# SOLEDNOID.net
KiCad netlist of a schematic drawn in Altium Designer
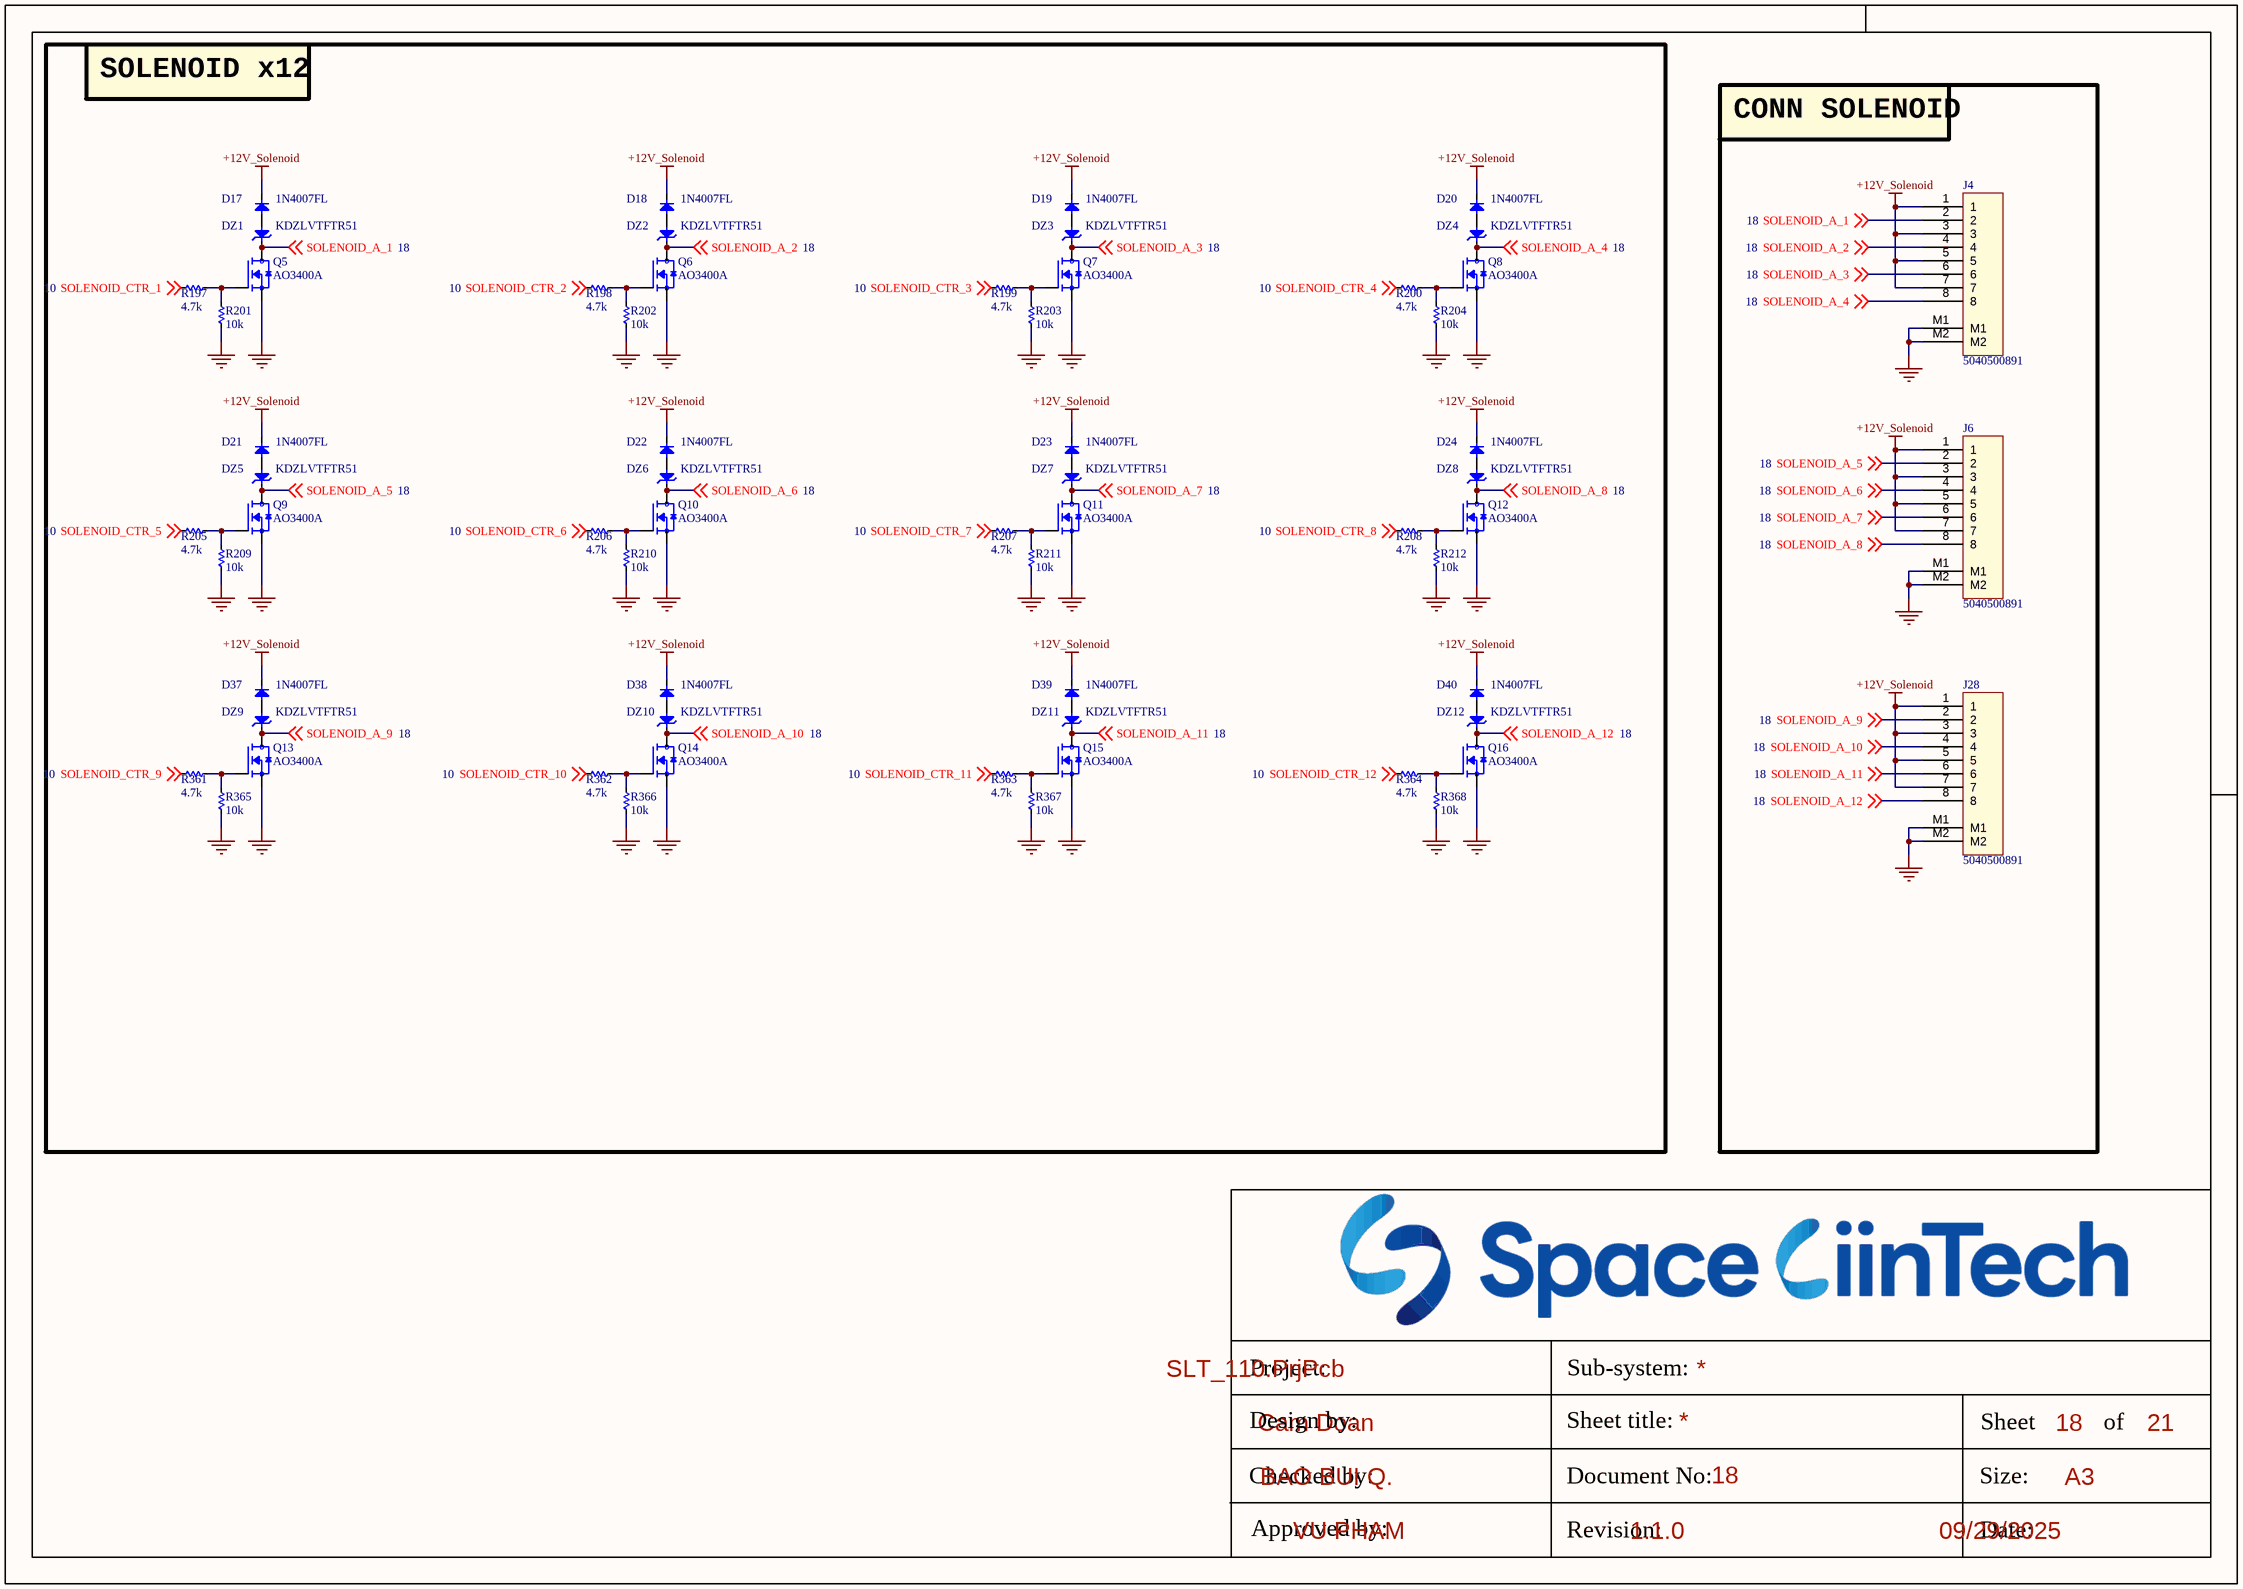
[diagram p0: SOLEDNOID.SchDoc]

(export (version "E")
  (design (tool "Eeschema 10.0.6"))
  (components
    (comp (ref "D17")
      (value "1N4007FL")
      (footprint "SOD3717X145N")
      (description "Default Diode")
      (fields (field (name "PUBLISHER") "Altium Limited"))
      (libsource (lib "LABLIB") (part "Diode SMD"))
    )
    (comp (ref "D18")
      (value "1N4007FL")
      (footprint "SOD3717X145N")
      (description "Default Diode")
      (fields (field (name "PUBLISHER") "Altium Limited"))
      (libsource (lib "LABLIB") (part "Diode SMD"))
    )
    (comp (ref "D19")
      (value "1N4007FL")
      (footprint "SOD3717X145N")
      (description "Default Diode")
      (fields (field (name "PUBLISHER") "Altium Limited"))
      (libsource (lib "LABLIB") (part "Diode SMD"))
    )
    (comp (ref "D20")
      (value "1N4007FL")
      (footprint "SOD3717X145N")
      (description "Default Diode")
      (fields (field (name "PUBLISHER") "Altium Limited"))
      (libsource (lib "LABLIB") (part "Diode SMD"))
    )
    (comp (ref "D21")
      (value "1N4007FL")
      (footprint "SOD3717X145N")
      (description "Default Diode")
      (fields (field (name "PUBLISHER") "Altium Limited"))
      (libsource (lib "LABLIB") (part "Diode SMD"))
    )
    (comp (ref "D22")
      (value "1N4007FL")
      (footprint "SOD3717X145N")
      (description "Default Diode")
      (fields (field (name "PUBLISHER") "Altium Limited"))
      (libsource (lib "LABLIB") (part "Diode SMD"))
    )
    (comp (ref "D23")
      (value "1N4007FL")
      (footprint "SOD3717X145N")
      (description "Default Diode")
      (fields (field (name "PUBLISHER") "Altium Limited"))
      (libsource (lib "LABLIB") (part "Diode SMD"))
    )
    (comp (ref "D24")
      (value "1N4007FL")
      (footprint "SOD3717X145N")
      (description "Default Diode")
      (fields (field (name "PUBLISHER") "Altium Limited"))
      (libsource (lib "LABLIB") (part "Diode SMD"))
    )
    (comp (ref "D37")
      (value "1N4007FL")
      (footprint "SOD3717X145N")
      (description "Default Diode")
      (fields (field (name "PUBLISHER") "Altium Limited"))
      (libsource (lib "LABLIB") (part "Diode SMD"))
    )
    (comp (ref "D38")
      (value "1N4007FL")
      (footprint "SOD3717X145N")
      (description "Default Diode")
      (fields (field (name "PUBLISHER") "Altium Limited"))
      (libsource (lib "LABLIB") (part "Diode SMD"))
    )
    (comp (ref "D39")
      (value "1N4007FL")
      (footprint "SOD3717X145N")
      (description "Default Diode")
      (fields (field (name "PUBLISHER") "Altium Limited"))
      (libsource (lib "LABLIB") (part "Diode SMD"))
    )
    (comp (ref "D40")
      (value "1N4007FL")
      (footprint "SOD3717X145N")
      (description "Default Diode")
      (fields (field (name "PUBLISHER") "Altium Limited"))
      (libsource (lib "LABLIB") (part "Diode SMD"))
    )
    (comp (ref "DZ1")
      (value "KDZLVTFTR51")
      (footprint "SOD3717X145N")
      (description "Zenner")
      (libsource (lib "LABLIB") (part "DIODE Zener"))
    )
    (comp (ref "DZ2")
      (value "KDZLVTFTR51")
      (footprint "SOD3717X145N")
      (description "Zenner")
      (libsource (lib "LABLIB") (part "DIODE Zener"))
    )
    (comp (ref "DZ3")
      (value "KDZLVTFTR51")
      (footprint "SOD3717X145N")
      (description "Zenner")
      (libsource (lib "LABLIB") (part "DIODE Zener"))
    )
    (comp (ref "DZ4")
      (value "KDZLVTFTR51")
      (footprint "SOD3717X145N")
      (description "Zenner")
      (libsource (lib "LABLIB") (part "DIODE Zener"))
    )
    (comp (ref "DZ5")
      (value "KDZLVTFTR51")
      (footprint "SOD3717X145N")
      (description "Zenner")
      (libsource (lib "LABLIB") (part "DIODE Zener"))
    )
    (comp (ref "DZ6")
      (value "KDZLVTFTR51")
      (footprint "SOD3717X145N")
      (description "Zenner")
      (libsource (lib "LABLIB") (part "DIODE Zener"))
    )
    (comp (ref "DZ7")
      (value "KDZLVTFTR51")
      (footprint "SOD3717X145N")
      (description "Zenner")
      (libsource (lib "LABLIB") (part "DIODE Zener"))
    )
    (comp (ref "DZ8")
      (value "KDZLVTFTR51")
      (footprint "SOD3717X145N")
      (description "Zenner")
      (libsource (lib "LABLIB") (part "DIODE Zener"))
    )
    (comp (ref "DZ9")
      (value "KDZLVTFTR51")
      (footprint "SOD3717X145N")
      (description "Zenner")
      (libsource (lib "LABLIB") (part "DIODE Zener"))
    )
    (comp (ref "DZ10")
      (value "KDZLVTFTR51")
      (footprint "SOD3717X145N")
      (description "Zenner")
      (libsource (lib "LABLIB") (part "DIODE Zener"))
    )
    (comp (ref "DZ11")
      (value "KDZLVTFTR51")
      (footprint "SOD3717X145N")
      (description "Zenner")
      (libsource (lib "LABLIB") (part "DIODE Zener"))
    )
    (comp (ref "DZ12")
      (value "KDZLVTFTR51")
      (footprint "SOD3717X145N")
      (description "Zenner")
      (libsource (lib "LABLIB") (part "DIODE Zener"))
    )
    (comp (ref "J4")
      (value "5040500891")
      (footprint "MOLEX_5040500891")
      (libsource (lib "LABLIB") (part "Header 8x1_2M"))
    )
    (comp (ref "J6")
      (value "5040500891")
      (footprint "MOLEX_5040500891")
      (libsource (lib "LABLIB") (part "Header 8x1_2M"))
    )
    (comp (ref "J28")
      (value "5040500891")
      (footprint "MOLEX_5040500891")
      (libsource (lib "LABLIB") (part "Header 8x1_2M"))
    )
    (comp (ref "Q5")
      (value "AO3400A")
      (footprint "SOT95P240X120-3N")
      (description "N-Channel 30 V 5.7A (Ta) 1.4W (Ta) Surface Mount SOT-23-3")
      (fields (field (name "MF") "Alpha & Omega Semiconductor"))
      (libsource (lib "new_component") (part "MOSFET_N"))
    )
    (comp (ref "Q6")
      (value "AO3400A")
      (footprint "SOT95P240X120-3N")
      (description "N-Channel 30 V 5.7A (Ta) 1.4W (Ta) Surface Mount SOT-23-3")
      (fields (field (name "MF") "Alpha & Omega Semiconductor"))
      (libsource (lib "new_component") (part "MOSFET_N"))
    )
    (comp (ref "Q7")
      (value "AO3400A")
      (footprint "SOT95P240X120-3N")
      (description "N-Channel 30 V 5.7A (Ta) 1.4W (Ta) Surface Mount SOT-23-3")
      (fields (field (name "MF") "Alpha & Omega Semiconductor"))
      (libsource (lib "new_component") (part "MOSFET_N"))
    )
    (comp (ref "Q8")
      (value "AO3400A")
      (footprint "SOT95P240X120-3N")
      (description "N-Channel 30 V 5.7A (Ta) 1.4W (Ta) Surface Mount SOT-23-3")
      (fields (field (name "MF") "Alpha & Omega Semiconductor"))
      (libsource (lib "new_component") (part "MOSFET_N"))
    )
    (comp (ref "Q9")
      (value "AO3400A")
      (footprint "SOT95P240X120-3N")
      (description "N-Channel 30 V 5.7A (Ta) 1.4W (Ta) Surface Mount SOT-23-3")
      (fields (field (name "MF") "Alpha & Omega Semiconductor"))
      (libsource (lib "new_component") (part "MOSFET_N"))
    )
    (comp (ref "Q10")
      (value "AO3400A")
      (footprint "SOT95P240X120-3N")
      (description "N-Channel 30 V 5.7A (Ta) 1.4W (Ta) Surface Mount SOT-23-3")
      (fields (field (name "MF") "Alpha & Omega Semiconductor"))
      (libsource (lib "new_component") (part "MOSFET_N"))
    )
    (comp (ref "Q11")
      (value "AO3400A")
      (footprint "SOT95P240X120-3N")
      (description "N-Channel 30 V 5.7A (Ta) 1.4W (Ta) Surface Mount SOT-23-3")
      (fields (field (name "MF") "Alpha & Omega Semiconductor"))
      (libsource (lib "new_component") (part "MOSFET_N"))
    )
    (comp (ref "Q12")
      (value "AO3400A")
      (footprint "SOT95P240X120-3N")
      (description "N-Channel 30 V 5.7A (Ta) 1.4W (Ta) Surface Mount SOT-23-3")
      (fields (field (name "MF") "Alpha & Omega Semiconductor"))
      (libsource (lib "new_component") (part "MOSFET_N"))
    )
    (comp (ref "Q13")
      (value "AO3400A")
      (footprint "SOT95P240X120-3N")
      (description "N-Channel 30 V 5.7A (Ta) 1.4W (Ta) Surface Mount SOT-23-3")
      (fields (field (name "MF") "Alpha & Omega Semiconductor"))
      (libsource (lib "new_component") (part "MOSFET_N"))
    )
    (comp (ref "Q14")
      (value "AO3400A")
      (footprint "SOT95P240X120-3N")
      (description "N-Channel 30 V 5.7A (Ta) 1.4W (Ta) Surface Mount SOT-23-3")
      (fields (field (name "MF") "Alpha & Omega Semiconductor"))
      (libsource (lib "new_component") (part "MOSFET_N"))
    )
    (comp (ref "Q15")
      (value "AO3400A")
      (footprint "SOT95P240X120-3N")
      (description "N-Channel 30 V 5.7A (Ta) 1.4W (Ta) Surface Mount SOT-23-3")
      (fields (field (name "MF") "Alpha & Omega Semiconductor"))
      (libsource (lib "new_component") (part "MOSFET_N"))
    )
    (comp (ref "Q16")
      (value "AO3400A")
      (footprint "SOT95P240X120-3N")
      (description "N-Channel 30 V 5.7A (Ta) 1.4W (Ta) Surface Mount SOT-23-3")
      (fields (field (name "MF") "Alpha & Omega Semiconductor"))
      (libsource (lib "new_component") (part "MOSFET_N"))
    )
    (comp (ref "R197")
      (value "4.7k")
      (footprint "RES_C_1005X40")
      (description "RES")
      (libsource (lib "LABLIB") (part "_RES_B_2"))
    )
    (comp (ref "R198")
      (value "4.7k")
      (footprint "RES_C_1005X40")
      (description "RES")
      (libsource (lib "LABLIB") (part "_RES_B_2"))
    )
    (comp (ref "R199")
      (value "4.7k")
      (footprint "RES_C_1005X40")
      (description "RES")
      (libsource (lib "LABLIB") (part "_RES_B_2"))
    )
    (comp (ref "R200")
      (value "4.7k")
      (footprint "RES_C_1005X40")
      (description "RES")
      (libsource (lib "LABLIB") (part "_RES_B_2"))
    )
    (comp (ref "R201")
      (value "10k")
      (footprint "RES_C_1005X40")
      (description "RES")
      (libsource (lib "LABLIB") (part "_RES_B_2"))
    )
    (comp (ref "R202")
      (value "10k")
      (footprint "RES_C_1005X40")
      (description "RES")
      (libsource (lib "LABLIB") (part "_RES_B_2"))
    )
    (comp (ref "R203")
      (value "10k")
      (footprint "RES_C_1005X40")
      (description "RES")
      (libsource (lib "LABLIB") (part "_RES_B_2"))
    )
    (comp (ref "R204")
      (value "10k")
      (footprint "RES_C_1005X40")
      (description "RES")
      (libsource (lib "LABLIB") (part "_RES_B_2"))
    )
    (comp (ref "R205")
      (value "4.7k")
      (footprint "RES_C_1005X40")
      (description "RES")
      (libsource (lib "LABLIB") (part "_RES_B_2"))
    )
    (comp (ref "R206")
      (value "4.7k")
      (footprint "RES_C_1005X40")
      (description "RES")
      (libsource (lib "LABLIB") (part "_RES_B_2"))
    )
    (comp (ref "R207")
      (value "4.7k")
      (footprint "RES_C_1005X40")
      (description "RES")
      (libsource (lib "LABLIB") (part "_RES_B_2"))
    )
    (comp (ref "R208")
      (value "4.7k")
      (footprint "RES_C_1005X40")
      (description "RES")
      (libsource (lib "LABLIB") (part "_RES_B_2"))
    )
    (comp (ref "R209")
      (value "10k")
      (footprint "RES_C_1005X40")
      (description "RES")
      (libsource (lib "LABLIB") (part "_RES_B_2"))
    )
    (comp (ref "R210")
      (value "10k")
      (footprint "RES_C_1005X40")
      (description "RES")
      (libsource (lib "LABLIB") (part "_RES_B_2"))
    )
    (comp (ref "R211")
      (value "10k")
      (footprint "RES_C_1005X40")
      (description "RES")
      (libsource (lib "LABLIB") (part "_RES_B_2"))
    )
    (comp (ref "R212")
      (value "10k")
      (footprint "RES_C_1005X40")
      (description "RES")
      (libsource (lib "LABLIB") (part "_RES_B_2"))
    )
    (comp (ref "R361")
      (value "4.7k")
      (footprint "RES_C_1005X40")
      (description "RES")
      (libsource (lib "LABLIB") (part "_RES_B_2"))
    )
    (comp (ref "R362")
      (value "4.7k")
      (footprint "RES_C_1005X40")
      (description "RES")
      (libsource (lib "LABLIB") (part "_RES_B_2"))
    )
    (comp (ref "R363")
      (value "4.7k")
      (footprint "RES_C_1005X40")
      (description "RES")
      (libsource (lib "LABLIB") (part "_RES_B_2"))
    )
    (comp (ref "R364")
      (value "4.7k")
      (footprint "RES_C_1005X40")
      (description "RES")
      (libsource (lib "LABLIB") (part "_RES_B_2"))
    )
    (comp (ref "R365")
      (value "10k")
      (footprint "RES_C_1005X40")
      (description "RES")
      (libsource (lib "LABLIB") (part "_RES_B_2"))
    )
    (comp (ref "R366")
      (value "10k")
      (footprint "RES_C_1005X40")
      (description "RES")
      (libsource (lib "LABLIB") (part "_RES_B_2"))
    )
    (comp (ref "R367")
      (value "10k")
      (footprint "RES_C_1005X40")
      (description "RES")
      (libsource (lib "LABLIB") (part "_RES_B_2"))
    )
    (comp (ref "R368")
      (value "10k")
      (footprint "RES_C_1005X40")
      (description "RES")
      (libsource (lib "LABLIB") (part "_RES_B_2"))
    )
  )
  (nets
    (net (code "1") (name "+12V_Solenoid") (class "Default")
      (node (ref "D17") (pin "1") (pinfunction "K_1") (pintype "passive"))
      (node (ref "D18") (pin "1") (pinfunction "K_1") (pintype "passive"))
      (node (ref "D19") (pin "1") (pinfunction "K_1") (pintype "passive"))
      (node (ref "D20") (pin "1") (pinfunction "K_1") (pintype "passive"))
      (node (ref "D21") (pin "1") (pinfunction "K_1") (pintype "passive"))
      (node (ref "D22") (pin "1") (pinfunction "K_1") (pintype "passive"))
      (node (ref "D23") (pin "1") (pinfunction "K_1") (pintype "passive"))
      (node (ref "D24") (pin "1") (pinfunction "K_1") (pintype "passive"))
      (node (ref "D37") (pin "1") (pinfunction "K_1") (pintype "passive"))
      (node (ref "D38") (pin "1") (pinfunction "K_1") (pintype "passive"))
      (node (ref "D39") (pin "1") (pinfunction "K_1") (pintype "passive"))
      (node (ref "D40") (pin "1") (pinfunction "K_1") (pintype "passive"))
      (node (ref "J28") (pin "1") (pinfunction "1_1") (pintype "passive"))
      (node (ref "J28") (pin "3") (pinfunction "3_3") (pintype "passive"))
      (node (ref "J28") (pin "5") (pinfunction "5_5") (pintype "passive"))
      (node (ref "J28") (pin "7") (pinfunction "7_7") (pintype "passive"))
      (node (ref "J4") (pin "1") (pinfunction "1_1") (pintype "passive"))
      (node (ref "J4") (pin "3") (pinfunction "3_3") (pintype "passive"))
      (node (ref "J4") (pin "5") (pinfunction "5_5") (pintype "passive"))
      (node (ref "J4") (pin "7") (pinfunction "7_7") (pintype "passive"))
      (node (ref "J6") (pin "1") (pinfunction "1_1") (pintype "passive"))
      (node (ref "J6") (pin "3") (pinfunction "3_3") (pintype "passive"))
      (node (ref "J6") (pin "5") (pinfunction "5_5") (pintype "passive"))
      (node (ref "J6") (pin "7") (pinfunction "7_7") (pintype "passive"))
    )
    (net (code "2") (name "GND") (class "Default")
      (node (ref "J28") (pin "M1") (pinfunction "M1_M1") (pintype "passive"))
      (node (ref "J28") (pin "M2") (pinfunction "M2_M2") (pintype "passive"))
      (node (ref "J4") (pin "M1") (pinfunction "M1_M1") (pintype "passive"))
      (node (ref "J4") (pin "M2") (pinfunction "M2_M2") (pintype "passive"))
      (node (ref "J6") (pin "M1") (pinfunction "M1_M1") (pintype "passive"))
      (node (ref "J6") (pin "M2") (pinfunction "M2_M2") (pintype "passive"))
      (node (ref "Q10") (pin "2") (pinfunction "S_2") (pintype "passive"))
      (node (ref "Q11") (pin "2") (pinfunction "S_2") (pintype "passive"))
      (node (ref "Q12") (pin "2") (pinfunction "S_2") (pintype "passive"))
      (node (ref "Q13") (pin "2") (pinfunction "S_2") (pintype "passive"))
      (node (ref "Q14") (pin "2") (pinfunction "S_2") (pintype "passive"))
      (node (ref "Q15") (pin "2") (pinfunction "S_2") (pintype "passive"))
      (node (ref "Q16") (pin "2") (pinfunction "S_2") (pintype "passive"))
      (node (ref "Q5") (pin "2") (pinfunction "S_2") (pintype "passive"))
      (node (ref "Q6") (pin "2") (pinfunction "S_2") (pintype "passive"))
      (node (ref "Q7") (pin "2") (pinfunction "S_2") (pintype "passive"))
      (node (ref "Q8") (pin "2") (pinfunction "S_2") (pintype "passive"))
      (node (ref "Q9") (pin "2") (pinfunction "S_2") (pintype "passive"))
      (node (ref "R201") (pin "1") (pinfunction "1_1") (pintype "passive"))
      (node (ref "R202") (pin "1") (pinfunction "1_1") (pintype "passive"))
      (node (ref "R203") (pin "1") (pinfunction "1_1") (pintype "passive"))
      (node (ref "R204") (pin "1") (pinfunction "1_1") (pintype "passive"))
      (node (ref "R209") (pin "1") (pinfunction "1_1") (pintype "passive"))
      (node (ref "R210") (pin "1") (pinfunction "1_1") (pintype "passive"))
      (node (ref "R211") (pin "1") (pinfunction "1_1") (pintype "passive"))
      (node (ref "R212") (pin "1") (pinfunction "1_1") (pintype "passive"))
      (node (ref "R365") (pin "1") (pinfunction "1_1") (pintype "passive"))
      (node (ref "R366") (pin "1") (pinfunction "1_1") (pintype "passive"))
      (node (ref "R367") (pin "1") (pinfunction "1_1") (pintype "passive"))
      (node (ref "R368") (pin "1") (pinfunction "1_1") (pintype "passive"))
    )
    (net (code "3") (name "Net-(D17-A)") (class "Default")
      (node (ref "D17") (pin "2") (pinfunction "A_2") (pintype "passive"))
      (node (ref "DZ1") (pin "2") (pinfunction "A_2") (pintype "passive"))
    )
    (net (code "4") (name "Net-(D18-A)") (class "Default")
      (node (ref "D18") (pin "2") (pinfunction "A_2") (pintype "passive"))
      (node (ref "DZ2") (pin "2") (pinfunction "A_2") (pintype "passive"))
    )
    (net (code "5") (name "Net-(D19-A)") (class "Default")
      (node (ref "D19") (pin "2") (pinfunction "A_2") (pintype "passive"))
      (node (ref "DZ3") (pin "2") (pinfunction "A_2") (pintype "passive"))
    )
    (net (code "6") (name "Net-(D20-A)") (class "Default")
      (node (ref "D20") (pin "2") (pinfunction "A_2") (pintype "passive"))
      (node (ref "DZ4") (pin "2") (pinfunction "A_2") (pintype "passive"))
    )
    (net (code "7") (name "Net-(D21-A)") (class "Default")
      (node (ref "D21") (pin "2") (pinfunction "A_2") (pintype "passive"))
      (node (ref "DZ5") (pin "2") (pinfunction "A_2") (pintype "passive"))
    )
    (net (code "8") (name "Net-(D22-A)") (class "Default")
      (node (ref "D22") (pin "2") (pinfunction "A_2") (pintype "passive"))
      (node (ref "DZ6") (pin "2") (pinfunction "A_2") (pintype "passive"))
    )
    (net (code "9") (name "Net-(D23-A)") (class "Default")
      (node (ref "D23") (pin "2") (pinfunction "A_2") (pintype "passive"))
      (node (ref "DZ7") (pin "2") (pinfunction "A_2") (pintype "passive"))
    )
    (net (code "10") (name "Net-(D24-A)") (class "Default")
      (node (ref "D24") (pin "2") (pinfunction "A_2") (pintype "passive"))
      (node (ref "DZ8") (pin "2") (pinfunction "A_2") (pintype "passive"))
    )
    (net (code "11") (name "Net-(D37-A)") (class "Default")
      (node (ref "D37") (pin "2") (pinfunction "A_2") (pintype "passive"))
      (node (ref "DZ9") (pin "2") (pinfunction "A_2") (pintype "passive"))
    )
    (net (code "12") (name "Net-(D38-A)") (class "Default")
      (node (ref "D38") (pin "2") (pinfunction "A_2") (pintype "passive"))
      (node (ref "DZ10") (pin "2") (pinfunction "A_2") (pintype "passive"))
    )
    (net (code "13") (name "Net-(D39-A)") (class "Default")
      (node (ref "D39") (pin "2") (pinfunction "A_2") (pintype "passive"))
      (node (ref "DZ11") (pin "2") (pinfunction "A_2") (pintype "passive"))
    )
    (net (code "14") (name "Net-(D40-A)") (class "Default")
      (node (ref "D40") (pin "2") (pinfunction "A_2") (pintype "passive"))
      (node (ref "DZ12") (pin "2") (pinfunction "A_2") (pintype "passive"))
    )
    (net (code "15") (name "Net-(Q5-G)") (class "Default")
      (node (ref "Q5") (pin "1") (pinfunction "G_1") (pintype "passive"))
      (node (ref "R197") (pin "1") (pinfunction "1_1") (pintype "passive"))
      (node (ref "R201") (pin "2") (pinfunction "2_2") (pintype "passive"))
    )
    (net (code "16") (name "Net-(Q6-G)") (class "Default")
      (node (ref "Q6") (pin "1") (pinfunction "G_1") (pintype "passive"))
      (node (ref "R198") (pin "1") (pinfunction "1_1") (pintype "passive"))
      (node (ref "R202") (pin "2") (pinfunction "2_2") (pintype "passive"))
    )
    (net (code "17") (name "Net-(Q7-G)") (class "Default")
      (node (ref "Q7") (pin "1") (pinfunction "G_1") (pintype "passive"))
      (node (ref "R199") (pin "1") (pinfunction "1_1") (pintype "passive"))
      (node (ref "R203") (pin "2") (pinfunction "2_2") (pintype "passive"))
    )
    (net (code "18") (name "Net-(Q8-G)") (class "Default")
      (node (ref "Q8") (pin "1") (pinfunction "G_1") (pintype "passive"))
      (node (ref "R200") (pin "1") (pinfunction "1_1") (pintype "passive"))
      (node (ref "R204") (pin "2") (pinfunction "2_2") (pintype "passive"))
    )
    (net (code "19") (name "Net-(Q9-G)") (class "Default")
      (node (ref "Q9") (pin "1") (pinfunction "G_1") (pintype "passive"))
      (node (ref "R205") (pin "1") (pinfunction "1_1") (pintype "passive"))
      (node (ref "R209") (pin "2") (pinfunction "2_2") (pintype "passive"))
    )
    (net (code "20") (name "Net-(Q10-G)") (class "Default")
      (node (ref "Q10") (pin "1") (pinfunction "G_1") (pintype "passive"))
      (node (ref "R206") (pin "1") (pinfunction "1_1") (pintype "passive"))
      (node (ref "R210") (pin "2") (pinfunction "2_2") (pintype "passive"))
    )
    (net (code "21") (name "Net-(Q11-G)") (class "Default")
      (node (ref "Q11") (pin "1") (pinfunction "G_1") (pintype "passive"))
      (node (ref "R207") (pin "1") (pinfunction "1_1") (pintype "passive"))
      (node (ref "R211") (pin "2") (pinfunction "2_2") (pintype "passive"))
    )
    (net (code "22") (name "Net-(Q12-G)") (class "Default")
      (node (ref "Q12") (pin "1") (pinfunction "G_1") (pintype "passive"))
      (node (ref "R208") (pin "1") (pinfunction "1_1") (pintype "passive"))
      (node (ref "R212") (pin "2") (pinfunction "2_2") (pintype "passive"))
    )
    (net (code "23") (name "Net-(Q13-G)") (class "Default")
      (node (ref "Q13") (pin "1") (pinfunction "G_1") (pintype "passive"))
      (node (ref "R361") (pin "1") (pinfunction "1_1") (pintype "passive"))
      (node (ref "R365") (pin "2") (pinfunction "2_2") (pintype "passive"))
    )
    (net (code "24") (name "Net-(Q14-G)") (class "Default")
      (node (ref "Q14") (pin "1") (pinfunction "G_1") (pintype "passive"))
      (node (ref "R362") (pin "1") (pinfunction "1_1") (pintype "passive"))
      (node (ref "R366") (pin "2") (pinfunction "2_2") (pintype "passive"))
    )
    (net (code "25") (name "Net-(Q15-G)") (class "Default")
      (node (ref "Q15") (pin "1") (pinfunction "G_1") (pintype "passive"))
      (node (ref "R363") (pin "1") (pinfunction "1_1") (pintype "passive"))
      (node (ref "R367") (pin "2") (pinfunction "2_2") (pintype "passive"))
    )
    (net (code "26") (name "Net-(Q16-G)") (class "Default")
      (node (ref "Q16") (pin "1") (pinfunction "G_1") (pintype "passive"))
      (node (ref "R364") (pin "1") (pinfunction "1_1") (pintype "passive"))
      (node (ref "R368") (pin "2") (pinfunction "2_2") (pintype "passive"))
    )
    (net (code "27") (name "SOLENOID_A_1") (class "Default")
      (node (ref "DZ1") (pin "1") (pinfunction "K_1") (pintype "passive"))
      (node (ref "J4") (pin "2") (pinfunction "2_2") (pintype "passive"))
      (node (ref "Q5") (pin "3") (pinfunction "D_3") (pintype "passive"))
    )
    (net (code "28") (name "SOLENOID_A_2") (class "Default")
      (node (ref "DZ2") (pin "1") (pinfunction "K_1") (pintype "passive"))
      (node (ref "J4") (pin "4") (pinfunction "4_4") (pintype "passive"))
      (node (ref "Q6") (pin "3") (pinfunction "D_3") (pintype "passive"))
    )
    (net (code "29") (name "SOLENOID_A_3") (class "Default")
      (node (ref "DZ3") (pin "1") (pinfunction "K_1") (pintype "passive"))
      (node (ref "J4") (pin "6") (pinfunction "6_6") (pintype "passive"))
      (node (ref "Q7") (pin "3") (pinfunction "D_3") (pintype "passive"))
    )
    (net (code "30") (name "SOLENOID_A_4") (class "Default")
      (node (ref "DZ4") (pin "1") (pinfunction "K_1") (pintype "passive"))
      (node (ref "J4") (pin "8") (pinfunction "8_8") (pintype "passive"))
      (node (ref "Q8") (pin "3") (pinfunction "D_3") (pintype "passive"))
    )
    (net (code "31") (name "SOLENOID_A_5") (class "Default")
      (node (ref "DZ5") (pin "1") (pinfunction "K_1") (pintype "passive"))
      (node (ref "J6") (pin "2") (pinfunction "2_2") (pintype "passive"))
      (node (ref "Q9") (pin "3") (pinfunction "D_3") (pintype "passive"))
    )
    (net (code "32") (name "SOLENOID_A_6") (class "Default")
      (node (ref "DZ6") (pin "1") (pinfunction "K_1") (pintype "passive"))
      (node (ref "J6") (pin "4") (pinfunction "4_4") (pintype "passive"))
      (node (ref "Q10") (pin "3") (pinfunction "D_3") (pintype "passive"))
    )
    (net (code "33") (name "SOLENOID_A_7") (class "Default")
      (node (ref "DZ7") (pin "1") (pinfunction "K_1") (pintype "passive"))
      (node (ref "J6") (pin "6") (pinfunction "6_6") (pintype "passive"))
      (node (ref "Q11") (pin "3") (pinfunction "D_3") (pintype "passive"))
    )
    (net (code "34") (name "SOLENOID_A_8") (class "Default")
      (node (ref "DZ8") (pin "1") (pinfunction "K_1") (pintype "passive"))
      (node (ref "J6") (pin "8") (pinfunction "8_8") (pintype "passive"))
      (node (ref "Q12") (pin "3") (pinfunction "D_3") (pintype "passive"))
    )
    (net (code "35") (name "SOLENOID_A_9") (class "Default")
      (node (ref "DZ9") (pin "1") (pinfunction "K_1") (pintype "passive"))
      (node (ref "J28") (pin "2") (pinfunction "2_2") (pintype "passive"))
      (node (ref "Q13") (pin "3") (pinfunction "D_3") (pintype "passive"))
    )
    (net (code "36") (name "SOLENOID_A_10") (class "Default")
      (node (ref "DZ10") (pin "1") (pinfunction "K_1") (pintype "passive"))
      (node (ref "J28") (pin "4") (pinfunction "4_4") (pintype "passive"))
      (node (ref "Q14") (pin "3") (pinfunction "D_3") (pintype "passive"))
    )
    (net (code "37") (name "SOLENOID_A_11") (class "Default")
      (node (ref "DZ11") (pin "1") (pinfunction "K_1") (pintype "passive"))
      (node (ref "J28") (pin "6") (pinfunction "6_6") (pintype "passive"))
      (node (ref "Q15") (pin "3") (pinfunction "D_3") (pintype "passive"))
    )
    (net (code "38") (name "SOLENOID_A_12") (class "Default")
      (node (ref "DZ12") (pin "1") (pinfunction "K_1") (pintype "passive"))
      (node (ref "J28") (pin "8") (pinfunction "8_8") (pintype "passive"))
      (node (ref "Q16") (pin "3") (pinfunction "D_3") (pintype "passive"))
    )
    (net (code "39") (name "SOLENOID_CTR_1") (class "Default")
      (node (ref "R197") (pin "2") (pinfunction "2_2") (pintype "passive"))
    )
    (net (code "40") (name "SOLENOID_CTR_2") (class "Default")
      (node (ref "R198") (pin "2") (pinfunction "2_2") (pintype "passive"))
    )
    (net (code "41") (name "SOLENOID_CTR_3") (class "Default")
      (node (ref "R199") (pin "2") (pinfunction "2_2") (pintype "passive"))
    )
    (net (code "42") (name "SOLENOID_CTR_4") (class "Default")
      (node (ref "R200") (pin "2") (pinfunction "2_2") (pintype "passive"))
    )
    (net (code "43") (name "SOLENOID_CTR_5") (class "Default")
      (node (ref "R205") (pin "2") (pinfunction "2_2") (pintype "passive"))
    )
    (net (code "44") (name "SOLENOID_CTR_6") (class "Default")
      (node (ref "R206") (pin "2") (pinfunction "2_2") (pintype "passive"))
    )
    (net (code "45") (name "SOLENOID_CTR_7") (class "Default")
      (node (ref "R207") (pin "2") (pinfunction "2_2") (pintype "passive"))
    )
    (net (code "46") (name "SOLENOID_CTR_8") (class "Default")
      (node (ref "R208") (pin "2") (pinfunction "2_2") (pintype "passive"))
    )
    (net (code "47") (name "SOLENOID_CTR_9") (class "Default")
      (node (ref "R361") (pin "2") (pinfunction "2_2") (pintype "passive"))
    )
    (net (code "48") (name "SOLENOID_CTR_10") (class "Default")
      (node (ref "R362") (pin "2") (pinfunction "2_2") (pintype "passive"))
    )
    (net (code "49") (name "SOLENOID_CTR_11") (class "Default")
      (node (ref "R363") (pin "2") (pinfunction "2_2") (pintype "passive"))
    )
    (net (code "50") (name "SOLENOID_CTR_12") (class "Default")
      (node (ref "R364") (pin "2") (pinfunction "2_2") (pintype "passive"))
    )
  )
)
